# PCB_1e.net
KiCad netlist of a schematic drawn in EAGLE
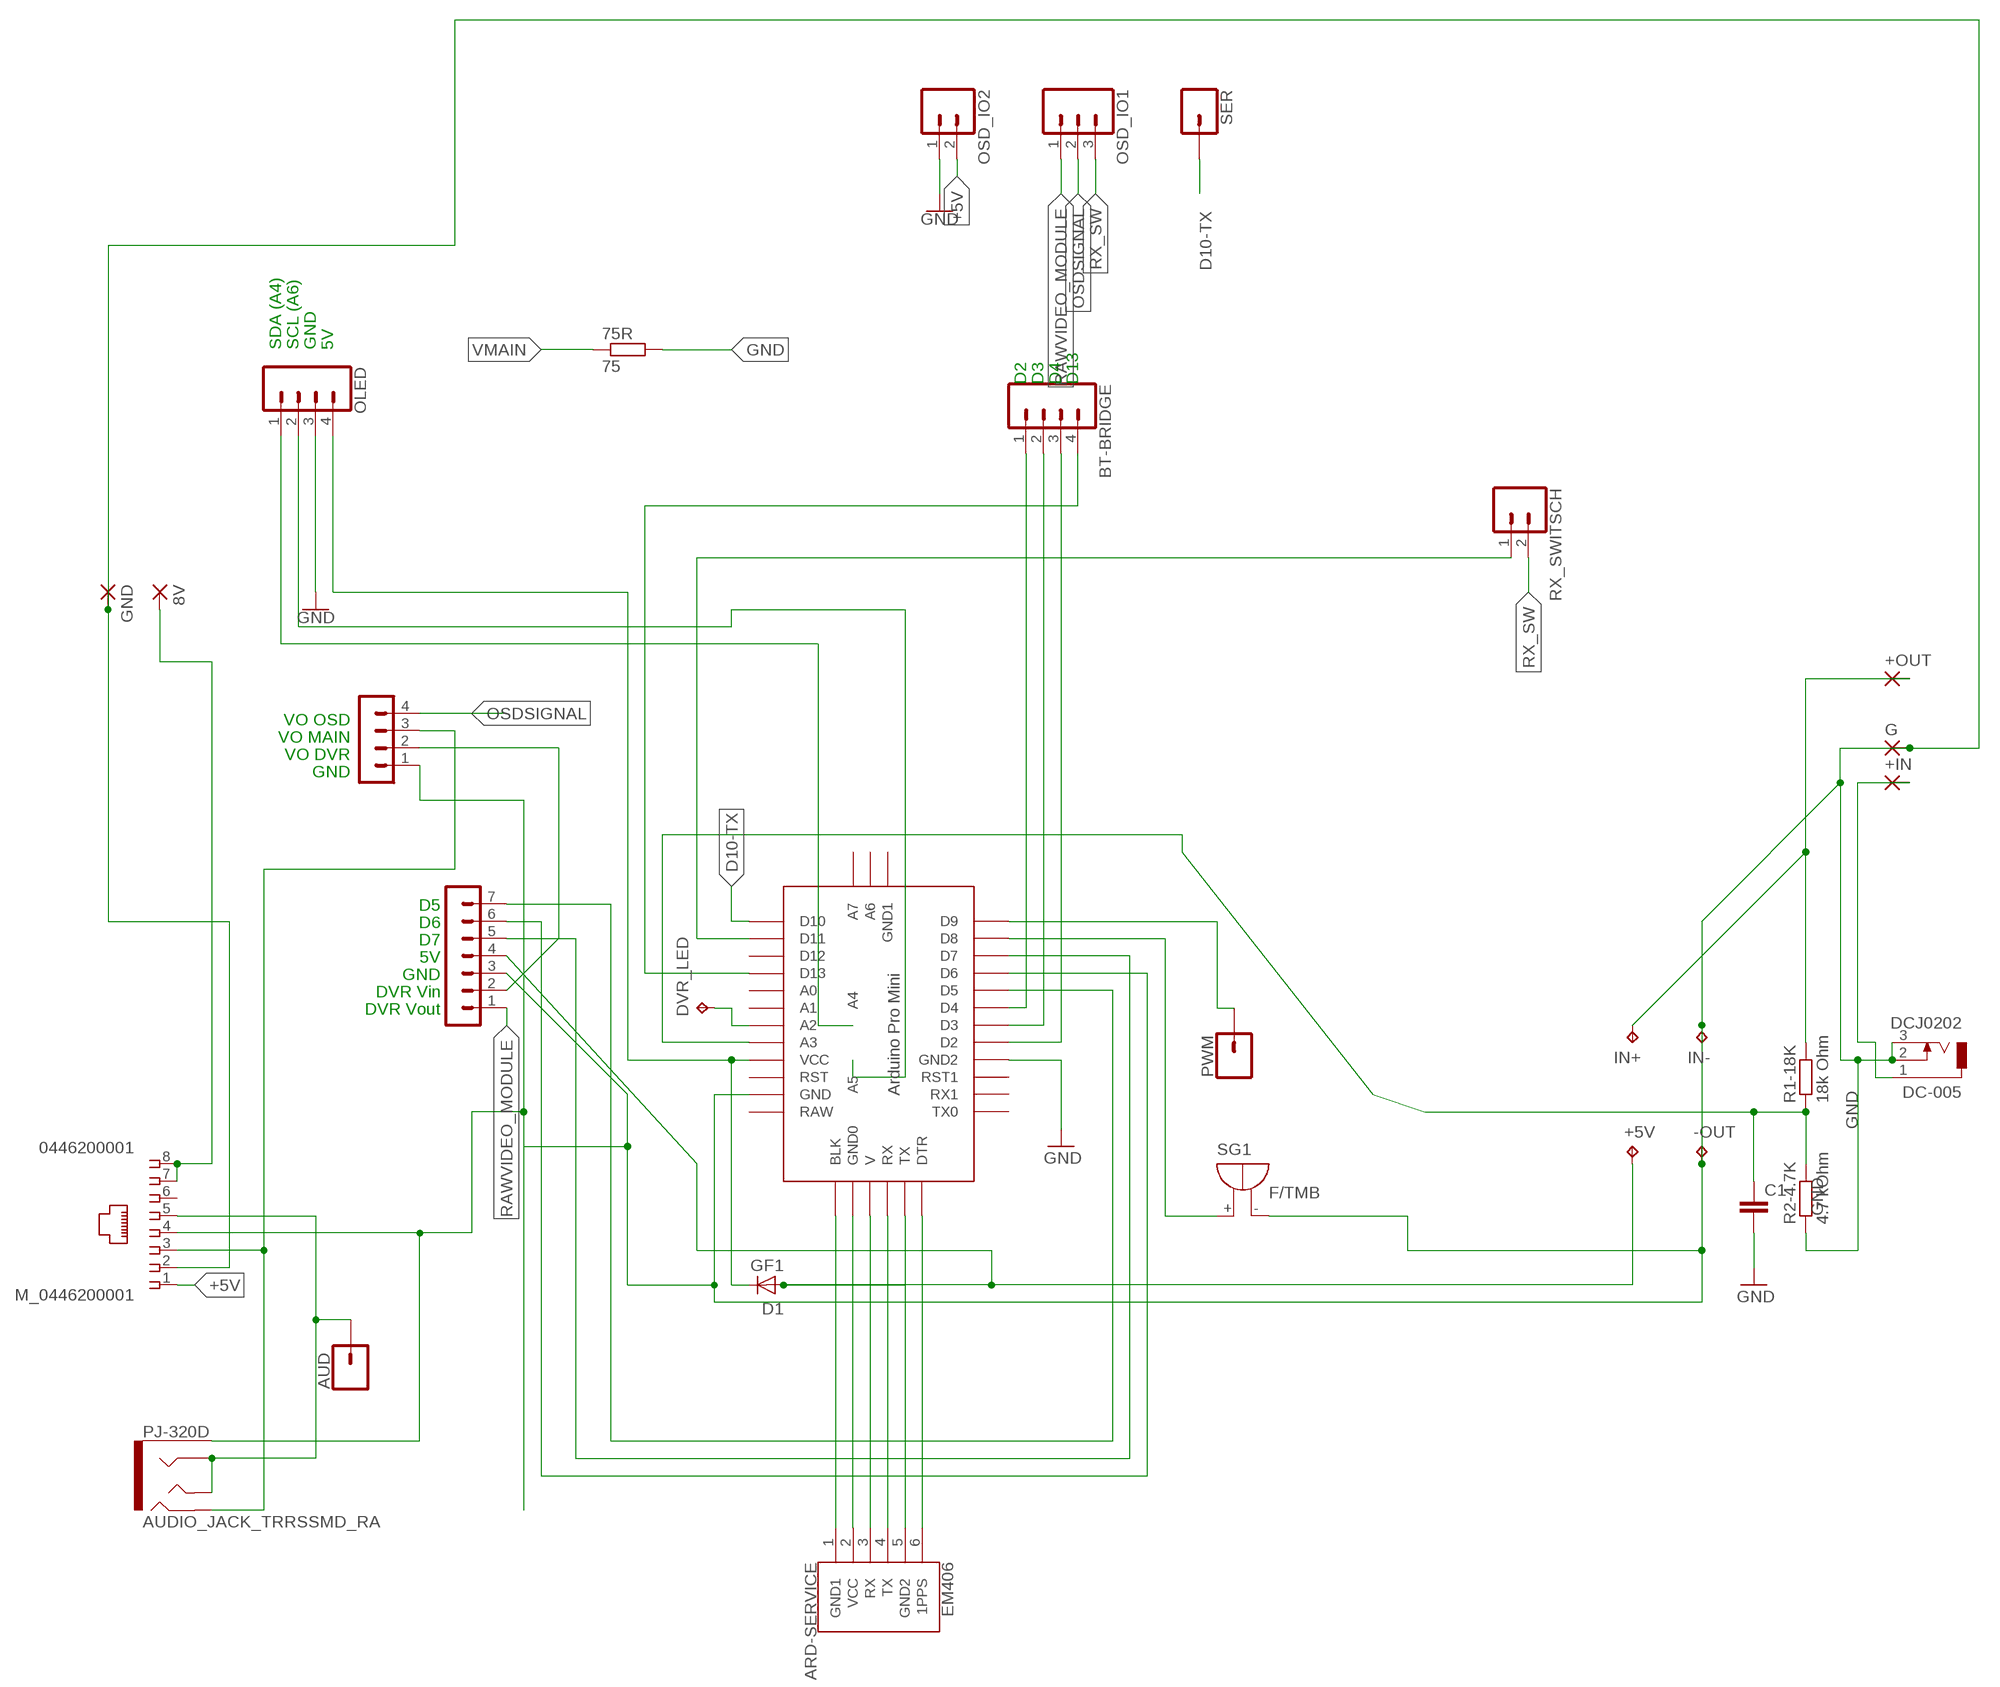
[diagram p0: schematic, sheet 1]

(export (version "E")
  (design (tool "Eeschema 10.0.6"))
  (components
    (comp (ref "+5V")
      (value "TPTP20SQ")
      (footprint "eagle-import:TP20SQ")
      (libsource (lib "eagle-import") (part "TPTP20SQ"))
    )
    (comp (ref "+IN")
      (value "2,54/1,1")
      (footprint "eagle-import:2,54_1,1")
      (libsource (lib "eagle-import") (part "2,54/1,1"))
    )
    (comp (ref "+OUT")
      (value "2,54/1,1")
      (footprint "eagle-import:2,54_1,1")
      (libsource (lib "eagle-import") (part "2,54/1,1"))
    )
    (comp (ref "-OUT")
      (value "TPTP20SQ")
      (footprint "eagle-import:TP20SQ")
      (libsource (lib "eagle-import") (part "TPTP20SQ"))
    )
    (comp (ref "8V")
      (value "2,54/1,1")
      (footprint "eagle-import:2,54_1,1")
      (libsource (lib "eagle-import") (part "2,54/1,1"))
    )
    (comp (ref "75R")
      (value "75")
      (footprint "eagle-import:R0603")
      (libsource (lib "eagle-import") (part "resistor_348_R-EU_R0603"))
    )
    (comp (ref "ARD-SERVICE")
      (value "EM406")
      (footprint "eagle-import:1X06-1MM")
      (libsource (lib "eagle-import") (part "EM406"))
    )
    (comp (ref "AUD")
      (value "CONN_01")
      (footprint "eagle-import:1X01")
      (libsource (lib "eagle-import") (part "CONN_01"))
    )
    (comp (ref "BT-BRIDGE")
      (value "CONN_04")
      (footprint "eagle-import:1X04")
      (libsource (lib "eagle-import") (part "CONN_04"))
    )
    (comp (ref "C1")
      (value "C-EUC1206K")
      (footprint "eagle-import:C1206K")
      (libsource (lib "eagle-import") (part "C-EUC1206K"))
    )
    (comp (ref "D1")
      (value "GF1")
      (footprint "eagle-import:SMA-DO214AC")
      (libsource (lib "eagle-import") (part "GF1"))
    )
    (comp (ref "DC-005")
      (value "DCJ0202")
      (footprint "eagle-import:DCJ0202")
      (libsource (lib "eagle-import") (part "DCJ0202"))
    )
    (comp (ref "DVR_LED")
      (value "TPTP20SQ")
      (footprint "eagle-import:TP20SQ")
      (libsource (lib "eagle-import") (part "TPTP20SQ"))
    )
    (comp (ref "G")
      (value "2,54/1,1")
      (footprint "eagle-import:2,54_1,1")
      (libsource (lib "eagle-import") (part "2,54/1,1"))
    )
    (comp (ref "GND")
      (value "2,54/1,1")
      (footprint "eagle-import:2,54_1,1")
      (libsource (lib "eagle-import") (part "2,54/1,1"))
    )
    (comp (ref "IN+")
      (value "TPTP20SQ")
      (footprint "eagle-import:TP20SQ")
      (libsource (lib "eagle-import") (part "TPTP20SQ"))
    )
    (comp (ref "IN-")
      (value "TPTP20SQ")
      (footprint "eagle-import:TP20SQ")
      (libsource (lib "eagle-import") (part "TPTP20SQ"))
    )
    (comp (ref "MODULE-IO")
      (value "MA07-1")
      (footprint "eagle-import:MA07-1")
      (libsource (lib "eagle-import") (part "MA07-1"))
    )
    (comp (ref "M_0446200001")
      (value "0446200001")
      (footprint "eagle-import:0446200001")
      (fields (field (name "MF") "MOLEX"))
      (libsource (lib "eagle-import") (part "0446200001"))
    )
    (comp (ref "OLED")
      (value "CONN_04")
      (footprint "eagle-import:1X04")
      (libsource (lib "eagle-import") (part "CONN_04"))
    )
    (comp (ref "OSD_IO1")
      (value "CONN_03")
      (footprint "eagle-import:1X03")
      (libsource (lib "eagle-import") (part "CONN_03"))
    )
    (comp (ref "OSD_IO2")
      (value "CONN_02")
      (footprint "eagle-import:1X02")
      (libsource (lib "eagle-import") (part "CONN_02"))
    )
    (comp (ref "PJ-320D")
      (value "AUDIO_JACK_TRRSSMD_RA")
      (footprint "eagle-import:AUDIO_JACK_3.5MM_TRRS_SMD_RA")
      (libsource (lib "eagle-import") (part "AUDIO_JACK_TRRSSMD_RA"))
    )
    (comp (ref "PWM")
      (value "CONN_01")
      (footprint "eagle-import:1X01")
      (libsource (lib "eagle-import") (part "CONN_01"))
    )
    (comp (ref "R1-18K")
      (value "18k Ohm")
      (footprint "eagle-import:M1206")
      (libsource (lib "eagle-import") (part "R-EU_M1206"))
    )
    (comp (ref "R2-4.7K")
      (value "4.7 kOhm")
      (footprint "eagle-import:M1206")
      (libsource (lib "eagle-import") (part "R-EU_M1206"))
    )
    (comp (ref "RX_SWITSCH")
      (value "CONN_02")
      (footprint "eagle-import:1X02")
      (libsource (lib "eagle-import") (part "CONN_02"))
    )
    (comp (ref "SER")
      (value "CONN_01")
      (footprint "eagle-import:1X01")
      (libsource (lib "eagle-import") (part "CONN_01"))
    )
    (comp (ref "SG1")
      (value "F/TMB")
      (footprint "eagle-import:F_TMB")
      (libsource (lib "eagle-import") (part "F/TMB"))
    )
    (comp (ref "U$1")
      (value "ABK-PRO-MINI")
      (footprint "eagle-import:ABK-PRO-MINI")
      (libsource (lib "eagle-import") (part "ABK-PRO-MINI"))
    )
    (comp (ref "V-IO")
      (value "MA04-1")
      (footprint "eagle-import:MA04-1")
      (libsource (lib "eagle-import") (part "MA04-1"))
    )
  )
  (nets
    (net (code "1") (name "+5V") (class "Default")
      (node (ref "+5V") (pin "TP") (pinfunction "TP_TP") (pintype "input"))
      (node (ref "D1") (pin "A") (pinfunction "A_A") (pintype "passive"))
      (node (ref "MODULE-IO") (pin "4") (pinfunction "4_4") (pintype "passive"))
      (node (ref "M_0446200001") (pin "1") (pinfunction "1_1") (pintype "passive"))
      (node (ref "OSD_IO2") (pin "2") (pinfunction "2_2") (pintype "passive"))
    )
    (net (code "2") (name "D10-TX") (class "Default")
      (node (ref "SER") (pin "1") (pinfunction "1_1") (pintype "passive"))
      (node (ref "U$1") (pin "D10") (pinfunction "D10_D10") (pintype "bidirectional"))
    )
    (net (code "3") (name "GND") (class "Default")
      (node (ref "-OUT") (pin "TP") (pinfunction "TP_TP") (pintype "input"))
      (node (ref "75R") (pin "2") (pinfunction "2_2") (pintype "passive"))
      (node (ref "C1") (pin "2") (pinfunction "2_2") (pintype "passive"))
      (node (ref "DC-005") (pin "2") (pinfunction "2_2") (pintype "passive"))
      (node (ref "DC-005") (pin "3") (pinfunction "3_3") (pintype "passive"))
      (node (ref "G") (pin "1") (pinfunction "P_1") (pintype "passive"))
      (node (ref "GND") (pin "1") (pinfunction "P_1") (pintype "passive"))
      (node (ref "IN-") (pin "TP") (pinfunction "TP_TP") (pintype "input"))
      (node (ref "MODULE-IO") (pin "3") (pinfunction "3_3") (pintype "passive"))
      (node (ref "M_0446200001") (pin "2") (pinfunction "2_2") (pintype "passive"))
      (node (ref "M_0446200001") (pin "4") (pinfunction "4_4") (pintype "passive"))
      (node (ref "OLED") (pin "3") (pinfunction "3_3") (pintype "passive"))
      (node (ref "OSD_IO2") (pin "1") (pinfunction "1_1") (pintype "passive"))
      (node (ref "PJ-320D") (pin "EARTH") (pinfunction "EARTH_EARTH") (pintype "bidirectional"))
      (node (ref "R2-4.7K") (pin "1") (pinfunction "1_1") (pintype "passive"))
      (node (ref "SG1") (pin "-") (pinfunction "-_-") (pintype "passive"))
      (node (ref "U$1") (pin "GND") (pinfunction "GND_GND") (pintype "bidirectional"))
      (node (ref "U$1") (pin "GND1") (pinfunction "GND2_GND1") (pintype "bidirectional"))
      (node (ref "V-IO") (pin "1") (pinfunction "1_1") (pintype "passive"))
    )
    (net (code "4") (name "Net-(+IN-P)") (class "Default")
      (node (ref "+IN") (pin "1") (pinfunction "P_1") (pintype "passive"))
      (node (ref "DC-005") (pin "1") (pinfunction "1_1") (pintype "passive"))
    )
    (net (code "5") (name "Net-(+OUT-P)") (class "Default")
      (node (ref "+OUT") (pin "1") (pinfunction "P_1") (pintype "passive"))
      (node (ref "IN+") (pin "TP") (pinfunction "TP_TP") (pintype "input"))
      (node (ref "R1-18K") (pin "2") (pinfunction "2_2") (pintype "passive"))
    )
    (net (code "6") (name "Net-(8V-P)") (class "Default")
      (node (ref "8V") (pin "1") (pinfunction "P_1") (pintype "passive"))
      (node (ref "M_0446200001") (pin "7") (pinfunction "7_7") (pintype "passive"))
      (node (ref "M_0446200001") (pin "8") (pinfunction "8_8") (pintype "passive"))
    )
    (net (code "7") (name "Net-(ARD-SERVICE-1PPS)") (class "Default")
      (node (ref "ARD-SERVICE") (pin "6") (pinfunction "1PPS_6") (pintype "bidirectional"))
      (node (ref "U$1") (pin "DTR") (pinfunction "DTR_DTR") (pintype "bidirectional"))
    )
    (net (code "8") (name "Net-(ARD-SERVICE-GND1)") (class "Default")
      (node (ref "ARD-SERVICE") (pin "1") (pinfunction "GND1_1") (pintype "bidirectional"))
      (node (ref "U$1") (pin "BLK") (pinfunction "BLK_BLK") (pintype "bidirectional"))
    )
    (net (code "9") (name "Net-(ARD-SERVICE-GND2)") (class "Default")
      (node (ref "ARD-SERVICE") (pin "5") (pinfunction "GND2_5") (pintype "bidirectional"))
      (node (ref "U$1") (pin "TX01") (pinfunction "TX_TX01") (pintype "bidirectional"))
    )
    (net (code "10") (name "Net-(ARD-SERVICE-RX)") (class "Default")
      (node (ref "ARD-SERVICE") (pin "3") (pinfunction "RX_3") (pintype "bidirectional"))
      (node (ref "U$1") (pin "5V") (pinfunction "V_5V") (pintype "bidirectional"))
    )
    (net (code "11") (name "Net-(ARD-SERVICE-TX)") (class "Default")
      (node (ref "ARD-SERVICE") (pin "4") (pinfunction "TX_4") (pintype "bidirectional"))
      (node (ref "U$1") (pin "RX01") (pinfunction "RX_RX01") (pintype "bidirectional"))
    )
    (net (code "12") (name "Net-(ARD-SERVICE-VCC)") (class "Default")
      (node (ref "ARD-SERVICE") (pin "2") (pinfunction "VCC_2") (pintype "bidirectional"))
      (node (ref "U$1") (pin "G") (pinfunction "GND0_G") (pintype "bidirectional"))
    )
    (net (code "13") (name "Net-(AUD-Pad1)") (class "Default")
      (node (ref "AUD") (pin "1") (pinfunction "1_1") (pintype "passive"))
      (node (ref "M_0446200001") (pin "5") (pinfunction "5_5") (pintype "passive"))
      (node (ref "PJ-320D") (pin "RING1") (pinfunction "RING1_RING1") (pintype "bidirectional"))
      (node (ref "PJ-320D") (pin "TIP") (pinfunction "TIP_TIP") (pintype "bidirectional"))
    )
    (net (code "14") (name "Net-(BT-BRIDGE-Pad1)") (class "Default")
      (node (ref "BT-BRIDGE") (pin "1") (pinfunction "1_1") (pintype "passive"))
      (node (ref "U$1") (pin "D4") (pinfunction "D4_D4") (pintype "bidirectional"))
    )
    (net (code "15") (name "Net-(BT-BRIDGE-Pad2)") (class "Default")
      (node (ref "BT-BRIDGE") (pin "2") (pinfunction "2_2") (pintype "passive"))
      (node (ref "U$1") (pin "D3") (pinfunction "D3_D3") (pintype "bidirectional"))
    )
    (net (code "16") (name "Net-(BT-BRIDGE-Pad3)") (class "Default")
      (node (ref "BT-BRIDGE") (pin "3") (pinfunction "3_3") (pintype "passive"))
      (node (ref "U$1") (pin "D2") (pinfunction "D2_D2") (pintype "bidirectional"))
    )
    (net (code "17") (name "Net-(BT-BRIDGE-Pad4)") (class "Default")
      (node (ref "BT-BRIDGE") (pin "4") (pinfunction "4_4") (pintype "passive"))
      (node (ref "U$1") (pin "D13") (pinfunction "D13_D13") (pintype "bidirectional"))
    )
    (net (code "18") (name "Net-(D1-C)") (class "Default")
      (node (ref "D1") (pin "K") (pinfunction "C_K") (pintype "passive"))
      (node (ref "OLED") (pin "4") (pinfunction "4_4") (pintype "passive"))
      (node (ref "U$1") (pin "VCC") (pinfunction "VCC_VCC") (pintype "bidirectional"))
    )
    (net (code "19") (name "Net-(MODULE-IO-Pad2)") (class "Default")
      (node (ref "MODULE-IO") (pin "2") (pinfunction "2_2") (pintype "passive"))
      (node (ref "V-IO") (pin "2") (pinfunction "2_2") (pintype "passive"))
    )
    (net (code "20") (name "Net-(MODULE-IO-Pad5)") (class "Default")
      (node (ref "MODULE-IO") (pin "5") (pinfunction "5_5") (pintype "passive"))
      (node (ref "U$1") (pin "D7") (pinfunction "D7_D7") (pintype "bidirectional"))
    )
    (net (code "21") (name "Net-(MODULE-IO-Pad6)") (class "Default")
      (node (ref "MODULE-IO") (pin "6") (pinfunction "6_6") (pintype "passive"))
      (node (ref "U$1") (pin "D6") (pinfunction "D6_D6") (pintype "bidirectional"))
    )
    (net (code "22") (name "Net-(MODULE-IO-Pad7)") (class "Default")
      (node (ref "MODULE-IO") (pin "7") (pinfunction "7_7") (pintype "passive"))
      (node (ref "U$1") (pin "D5") (pinfunction "D5_D5") (pintype "bidirectional"))
    )
    (net (code "23") (name "Net-(OLED-Pad1)") (class "Default")
      (node (ref "OLED") (pin "1") (pinfunction "1_1") (pintype "passive"))
      (node (ref "U$1") (pin "A4") (pinfunction "A4_A4") (pintype "bidirectional"))
    )
    (net (code "24") (name "Net-(OLED-Pad2)") (class "Default")
      (node (ref "OLED") (pin "2") (pinfunction "2_2") (pintype "passive"))
      (node (ref "U$1") (pin "A5") (pinfunction "A5_A5") (pintype "bidirectional"))
    )
    (net (code "25") (name "Net-(PWM-Pad1)") (class "Default")
      (node (ref "PWM") (pin "1") (pinfunction "1_1") (pintype "passive"))
      (node (ref "U$1") (pin "D9") (pinfunction "D9_D9") (pintype "bidirectional"))
    )
    (net (code "26") (name "Net-(RX_SWITSCH-Pad1)") (class "Default")
      (node (ref "RX_SWITSCH") (pin "1") (pinfunction "1_1") (pintype "passive"))
      (node (ref "U$1") (pin "D11") (pinfunction "D11_D11") (pintype "bidirectional"))
    )
    (net (code "27") (name "Net-(SG1-Pad+)") (class "Default")
      (node (ref "SG1") (pin "+") (pinfunction "+_+") (pintype "passive"))
      (node (ref "U$1") (pin "D8") (pinfunction "D8_D8") (pintype "bidirectional"))
    )
    (net (code "28") (name "Net-(U$1-A2)") (class "Default")
      (node (ref "DVR_LED") (pin "TP") (pinfunction "TP_TP") (pintype "input"))
      (node (ref "U$1") (pin "A1") (pinfunction "A2_A1") (pintype "bidirectional"))
    )
    (net (code "29") (name "Net-(U$1-A3)") (class "Default")
      (node (ref "C1") (pin "1") (pinfunction "1_1") (pintype "passive"))
      (node (ref "R1-18K") (pin "1") (pinfunction "1_1") (pintype "passive"))
      (node (ref "R2-4.7K") (pin "2") (pinfunction "2_2") (pintype "passive"))
      (node (ref "U$1") (pin "A0") (pinfunction "A3_A0") (pintype "bidirectional"))
    )
    (net (code "30") (name "OSDSIGNAL") (class "Default")
      (node (ref "OSD_IO1") (pin "2") (pinfunction "2_2") (pintype "passive"))
      (node (ref "V-IO") (pin "4") (pinfunction "4_4") (pintype "passive"))
    )
    (net (code "31") (name "RAWVIDEO_MODULE") (class "Default")
      (node (ref "MODULE-IO") (pin "1") (pinfunction "1_1") (pintype "passive"))
      (node (ref "OSD_IO1") (pin "1") (pinfunction "1_1") (pintype "passive"))
    )
    (net (code "32") (name "RX_SW") (class "Default")
      (node (ref "OSD_IO1") (pin "3") (pinfunction "3_3") (pintype "passive"))
      (node (ref "RX_SWITSCH") (pin "2") (pinfunction "2_2") (pintype "passive"))
    )
    (net (code "33") (name "VMAIN") (class "Default")
      (node (ref "75R") (pin "1") (pinfunction "1_1") (pintype "passive"))
      (node (ref "M_0446200001") (pin "3") (pinfunction "3_3") (pintype "passive"))
      (node (ref "PJ-320D") (pin "RING2") (pinfunction "RING2_RING2") (pintype "bidirectional"))
      (node (ref "V-IO") (pin "3") (pinfunction "3_3") (pintype "passive"))
    )
    (net (code "34") (name "unconnected-(M_0446200001-Pad6)") (class "Default")
      (node (ref "M_0446200001") (pin "6") (pinfunction "6_6") (pintype "passive"))
    )
    (net (code "35") (name "unconnected-(U$1-A0-PadA3)") (class "Default")
      (node (ref "U$1") (pin "A3") (pinfunction "A0_A3") (pintype "bidirectional"))
    )
    (net (code "36") (name "unconnected-(U$1-A1-PadA2)") (class "Default")
      (node (ref "U$1") (pin "A2") (pinfunction "A1_A2") (pintype "bidirectional"))
    )
    (net (code "37") (name "unconnected-(U$1-GND1-PadGND4)") (class "Default")
      (node (ref "U$1") (pin "GND4") (pinfunction "GND1_GND4") (pintype "bidirectional"))
    )
    (net (code "38") (name "unconnected-(U$1-PadA6)") (class "Default")
      (node (ref "U$1") (pin "A6") (pinfunction "A6_A6") (pintype "bidirectional"))
    )
    (net (code "39") (name "unconnected-(U$1-PadA7)") (class "Default")
      (node (ref "U$1") (pin "A7") (pinfunction "A7_A7") (pintype "bidirectional"))
    )
    (net (code "40") (name "unconnected-(U$1-PadD12)") (class "Default")
      (node (ref "U$1") (pin "D12") (pinfunction "D12_D12") (pintype "bidirectional"))
    )
    (net (code "41") (name "unconnected-(U$1-PadRAW)") (class "Default")
      (node (ref "U$1") (pin "RAW") (pinfunction "RAW_RAW") (pintype "bidirectional"))
    )
    (net (code "42") (name "unconnected-(U$1-PadRST)") (class "Default")
      (node (ref "U$1") (pin "RST") (pinfunction "RST_RST") (pintype "bidirectional"))
    )
    (net (code "43") (name "unconnected-(U$1-PadRST1)") (class "Default")
      (node (ref "U$1") (pin "RST1") (pinfunction "RST1_RST1") (pintype "bidirectional"))
    )
    (net (code "44") (name "unconnected-(U$1-PadRX1)") (class "Default")
      (node (ref "U$1") (pin "RX1") (pinfunction "RX1_RX1") (pintype "bidirectional"))
    )
    (net (code "45") (name "unconnected-(U$1-PadTX0)") (class "Default")
      (node (ref "U$1") (pin "TX0") (pinfunction "TX0_TX0") (pintype "bidirectional"))
    )
  )
)
